# SOC_MIPI-CSI_I2C.net
KiCad netlist of a schematic drawn in Altium Designer
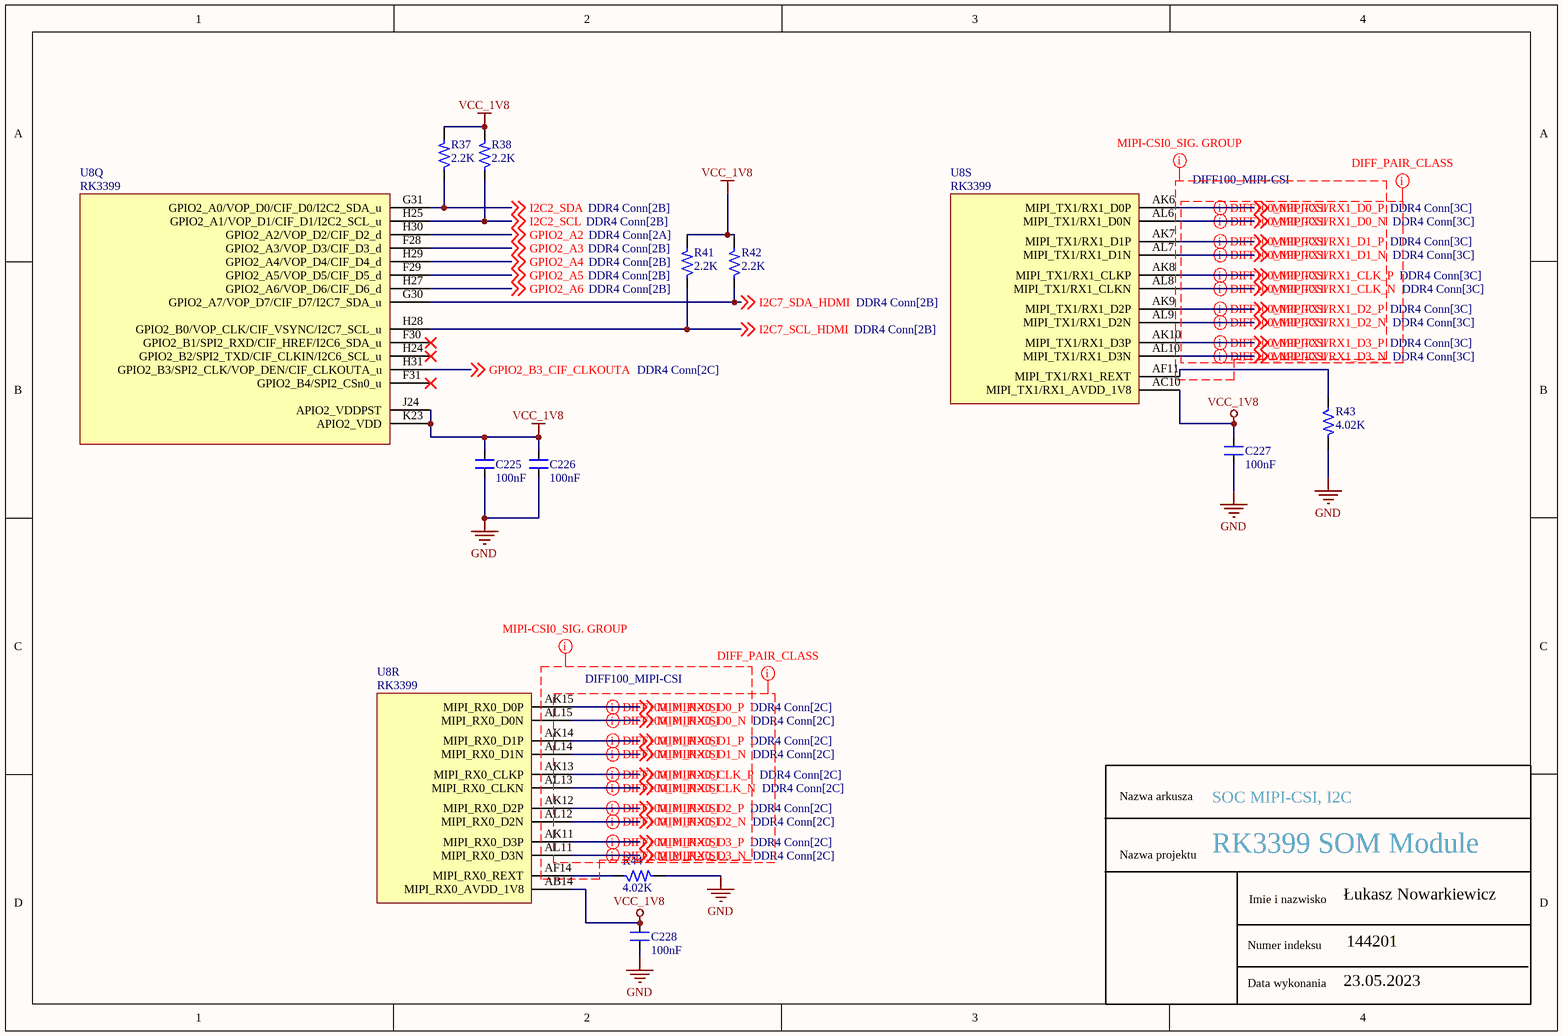
[diagram p0: SOC MIPI-CSI, I2C.SchDoc]

(export (version "E")
  (design (tool "Eeschema 10.0.6"))
  (components
    (comp (ref "C225")
      (value "100nF")
      (footprint "CAP_0201")
      (description "0.1µF ±10% 25V Ceramic Capacitor X5R 0201 (0603 Metric)")
      (fields
        (field (name "MANUFACTURER") "TDK Corporation")
        (field (name "MANUFACTURER PART NUMBER") "C0603X5R1E104K030BB")
      )
      (libsource (lib "RK3399 _Module_Intlib") (part "CAP_100nF-25V-10%-0201"))
    )
    (comp (ref "C226")
      (value "100nF")
      (footprint "CAP_0201")
      (description "0.1µF ±10% 25V Ceramic Capacitor X5R 0201 (0603 Metric)")
      (fields
        (field (name "MANUFACTURER") "TDK Corporation")
        (field (name "MANUFACTURER PART NUMBER") "C0603X5R1E104K030BB")
      )
      (libsource (lib "RK3399 _Module_Intlib") (part "CAP_100nF-25V-10%-0201"))
    )
    (comp (ref "C227")
      (value "100nF")
      (footprint "CAP_0201")
      (description "0.1µF ±10% 25V Ceramic Capacitor X5R 0201 (0603 Metric)")
      (fields
        (field (name "MANUFACTURER") "TDK Corporation")
        (field (name "MANUFACTURER PART NUMBER") "C0603X5R1E104K030BB")
      )
      (libsource (lib "RK3399 _Module_Intlib") (part "CAP_100nF-25V-10%-0201"))
    )
    (comp (ref "C228")
      (value "100nF")
      (footprint "CAP_0201")
      (description "0.1µF ±10% 25V Ceramic Capacitor X5R 0201 (0603 Metric)")
      (fields
        (field (name "MANUFACTURER") "TDK Corporation")
        (field (name "MANUFACTURER PART NUMBER") "C0603X5R1E104K030BB")
      )
      (libsource (lib "RK3399 _Module_Intlib") (part "CAP_100nF-25V-10%-0201"))
    )
    (comp (ref "R37")
      (value "2.2K")
      (footprint "RES_0201")
      (description "2.2 kOhms ±1% 0.05W, 1/20W Chip Resistor 0201 (0603 Metric) Thick Film")
      (fields
        (field (name "MANUFACTURER") "Stackpole Electronics Inc")
        (field (name "MANUFACTURER PART NUMBER") "RMCF0201FT2K20")
      )
      (libsource (lib "RK3399 _Module_Intlib") (part "RES_2.2K-0.05W-1%-0201"))
    )
    (comp (ref "R38")
      (value "2.2K")
      (footprint "RES_0201")
      (description "2.2 kOhms ±1% 0.05W, 1/20W Chip Resistor 0201 (0603 Metric) Thick Film")
      (fields
        (field (name "MANUFACTURER") "Stackpole Electronics Inc")
        (field (name "MANUFACTURER PART NUMBER") "RMCF0201FT2K20")
      )
      (libsource (lib "RK3399 _Module_Intlib") (part "RES_2.2K-0.05W-1%-0201"))
    )
    (comp (ref "R41")
      (value "2.2K")
      (footprint "RES_0201")
      (description "2.2 kOhms ±1% 0.05W, 1/20W Chip Resistor 0201 (0603 Metric) Thick Film")
      (fields
        (field (name "MANUFACTURER") "Stackpole Electronics Inc")
        (field (name "MANUFACTURER PART NUMBER") "RMCF0201FT2K20")
      )
      (libsource (lib "RK3399 _Module_Intlib") (part "RES_2.2K-0.05W-1%-0201"))
    )
    (comp (ref "R42")
      (value "2.2K")
      (footprint "RES_0201")
      (description "2.2 kOhms ±1% 0.05W, 1/20W Chip Resistor 0201 (0603 Metric) Thick Film")
      (fields
        (field (name "MANUFACTURER") "Stackpole Electronics Inc")
        (field (name "MANUFACTURER PART NUMBER") "RMCF0201FT2K20")
      )
      (libsource (lib "RK3399 _Module_Intlib") (part "RES_2.2K-0.05W-1%-0201"))
    )
    (comp (ref "R43")
      (value "4.02K")
      (footprint "RES_0201")
      (description "4.02 kOhms ±1% 0.05W, 1/20W Chip Resistor 0201 (0603 Metric) Thick Film")
      (fields
        (field (name "MANUFACTURER") "Yageo")
        (field (name "MANUFACTURER PART NUMBER") "RC0201FR-074K02L")
      )
      (libsource (lib "RK3399 _Module_Intlib") (part "RES_4.02K-0.05W-1%-0201"))
    )
    (comp (ref "R44")
      (value "4.02K")
      (footprint "RES_0201")
      (description "4.02 kOhms ±1% 0.05W, 1/20W Chip Resistor 0201 (0603 Metric) Thick Film")
      (fields
        (field (name "MANUFACTURER") "Yageo")
        (field (name "MANUFACTURER PART NUMBER") "RC0201FR-074K02L")
      )
      (libsource (lib "RK3399 _Module_Intlib") (part "RES_4.02K-0.05W-1%-0201"))
    )
    (comp (ref "U8")
      (value "RK3399")
      (footprint "FBGA828_23_826X826")
      (description "RK3399 is a low power, high performance processor for computing, personal mobile.")
      (fields (field (name "MANUFACTURER") "Rockchip"))
      (libsource (lib "EsteemPCB_SOM_Course_intlib") (part "IC_RK3399-FCBGA828"))
    )
  )
  (nets
    (net (code "1") (name "GND") (class "Default")
      (node (ref "C225") (pin "1") (pinfunction "1_1") (pintype "passive"))
      (node (ref "C226") (pin "1") (pinfunction "1_1") (pintype "passive"))
      (node (ref "C227") (pin "1") (pinfunction "1_1") (pintype "passive"))
      (node (ref "C228") (pin "1") (pinfunction "1_1") (pintype "passive"))
      (node (ref "R43") (pin "2") (pinfunction "2_2") (pintype "passive"))
      (node (ref "R44") (pin "2") (pinfunction "2_2") (pintype "passive"))
    )
    (net (code "2") (name "GPIO2_A2") (class "Default")
      (node (ref "U8") (pin "H30") (pinfunction "GPIO2_A2/VOP_D2/CIF_D2_d_H30") (pintype "passive"))
    )
    (net (code "3") (name "GPIO2_A3") (class "Default")
      (node (ref "U8") (pin "F28") (pinfunction "GPIO2_A3/VOP_D3/CIF_D3_d_F28") (pintype "passive"))
    )
    (net (code "4") (name "GPIO2_A4") (class "Default")
      (node (ref "U8") (pin "H29") (pinfunction "GPIO2_A4/VOP_D4/CIF_D4_d_H29") (pintype "passive"))
    )
    (net (code "5") (name "GPIO2_A5") (class "Default")
      (node (ref "U8") (pin "F29") (pinfunction "GPIO2_A5/VOP_D5/CIF_D5_d_F29") (pintype "passive"))
    )
    (net (code "6") (name "GPIO2_A6") (class "Default")
      (node (ref "U8") (pin "H27") (pinfunction "GPIO2_A6/VOP_D6/CIF_D6_d_H27") (pintype "passive"))
    )
    (net (code "7") (name "GPIO2_B3_CIF_CLKOUTA") (class "Default")
      (node (ref "U8") (pin "H31") (pinfunction "GPIO2_B3/SPI2_CLK/VOP_DEN/CIF_CLKOUTA_u_H31") (pintype "passive"))
    )
    (net (code "8") (name "I2C2_SCL") (class "Default")
      (node (ref "R38") (pin "1") (pinfunction "1_1") (pintype "passive"))
      (node (ref "U8") (pin "H25") (pinfunction "GPIO2_A1/VOP_D1/CIF_D1/I2C2_SCL_u_H25") (pintype "passive"))
    )
    (net (code "9") (name "I2C2_SDA") (class "Default")
      (node (ref "R37") (pin "1") (pinfunction "1_1") (pintype "passive"))
      (node (ref "U8") (pin "G31") (pinfunction "GPIO2_A0/VOP_D0/CIF_D0/I2C2_SDA_u_G31") (pintype "passive"))
    )
    (net (code "10") (name "I2C7_SCL_HDMI") (class "Default")
      (node (ref "R41") (pin "1") (pinfunction "1_1") (pintype "passive"))
      (node (ref "U8") (pin "H28") (pinfunction "GPIO2_B0/VOP_CLK/CIF_VSYNC/I2C7_SCL_u_H28") (pintype "passive"))
    )
    (net (code "11") (name "I2C7_SDA_HDMI") (class "Default")
      (node (ref "R42") (pin "1") (pinfunction "1_1") (pintype "passive"))
      (node (ref "U8") (pin "G30") (pinfunction "GPIO2_A7/VOP_D7/CIF_D7/I2C7_SDA_u_G30") (pintype "passive"))
    )
    (net (code "12") (name "MIPI_RX0_CLK_N") (class "Default")
      (node (ref "U8") (pin "AL13") (pinfunction "MIPI_RX0_CLKN_AL13") (pintype "passive"))
    )
    (net (code "13") (name "MIPI_RX0_CLK_P") (class "Default")
      (node (ref "U8") (pin "AK13") (pinfunction "MIPI_RX0_CLKP_AK13") (pintype "passive"))
    )
    (net (code "14") (name "MIPI_RX0_D0_N") (class "Default")
      (node (ref "U8") (pin "AL15") (pinfunction "MIPI_RX0_D0N_AL15") (pintype "passive"))
    )
    (net (code "15") (name "MIPI_RX0_D0_P") (class "Default")
      (node (ref "U8") (pin "AK15") (pinfunction "MIPI_RX0_D0P_AK15") (pintype "passive"))
    )
    (net (code "16") (name "MIPI_RX0_D1_N") (class "Default")
      (node (ref "U8") (pin "AL14") (pinfunction "MIPI_RX0_D1N_AL14") (pintype "passive"))
    )
    (net (code "17") (name "MIPI_RX0_D1_P") (class "Default")
      (node (ref "U8") (pin "AK14") (pinfunction "MIPI_RX0_D1P_AK14") (pintype "passive"))
    )
    (net (code "18") (name "MIPI_RX0_D2_N") (class "Default")
      (node (ref "U8") (pin "AL12") (pinfunction "MIPI_RX0_D2N_AL12") (pintype "passive"))
    )
    (net (code "19") (name "MIPI_RX0_D2_P") (class "Default")
      (node (ref "U8") (pin "AK12") (pinfunction "MIPI_RX0_D2P_AK12") (pintype "passive"))
    )
    (net (code "20") (name "MIPI_RX0_D3_N") (class "Default")
      (node (ref "U8") (pin "AL11") (pinfunction "MIPI_RX0_D3N_AL11") (pintype "passive"))
    )
    (net (code "21") (name "MIPI_RX0_D3_P") (class "Default")
      (node (ref "U8") (pin "AK11") (pinfunction "MIPI_RX0_D3P_AK11") (pintype "passive"))
    )
    (net (code "22") (name "MIPI_TX1{slash}RX1_CLK_N") (class "Default")
      (node (ref "U8") (pin "AL8") (pinfunction "MIPI_TX1/RX1_CLKN_AL8") (pintype "passive"))
    )
    (net (code "23") (name "MIPI_TX1{slash}RX1_CLK_P") (class "Default")
      (node (ref "U8") (pin "AK8") (pinfunction "MIPI_TX1/RX1_CLKP_AK8") (pintype "passive"))
    )
    (net (code "24") (name "MIPI_TX1{slash}RX1_D0_N") (class "Default")
      (node (ref "U8") (pin "AL6") (pinfunction "MIPI_TX1/RX1_D0N_AL6") (pintype "passive"))
    )
    (net (code "25") (name "MIPI_TX1{slash}RX1_D0_P") (class "Default")
      (node (ref "U8") (pin "AK6") (pinfunction "MIPI_TX1/RX1_D0P_AK6") (pintype "passive"))
    )
    (net (code "26") (name "MIPI_TX1{slash}RX1_D1_N") (class "Default")
      (node (ref "U8") (pin "AL7") (pinfunction "MIPI_TX1/RX1_D1N_AL7") (pintype "passive"))
    )
    (net (code "27") (name "MIPI_TX1{slash}RX1_D1_P") (class "Default")
      (node (ref "U8") (pin "AK7") (pinfunction "MIPI_TX1/RX1_D1P_AK7") (pintype "passive"))
    )
    (net (code "28") (name "MIPI_TX1{slash}RX1_D2_N") (class "Default")
      (node (ref "U8") (pin "AL9") (pinfunction "MIPI_TX1/RX1_D2N_AL9") (pintype "passive"))
    )
    (net (code "29") (name "MIPI_TX1{slash}RX1_D2_P") (class "Default")
      (node (ref "U8") (pin "AK9") (pinfunction "MIPI_TX1/RX1_D2P_AK9") (pintype "passive"))
    )
    (net (code "30") (name "MIPI_TX1{slash}RX1_D3_N") (class "Default")
      (node (ref "U8") (pin "AL10") (pinfunction "MIPI_TX1/RX1_D3N_AL10") (pintype "passive"))
    )
    (net (code "31") (name "MIPI_TX1{slash}RX1_D3_P") (class "Default")
      (node (ref "U8") (pin "AK10") (pinfunction "MIPI_TX1/RX1_D3P_AK10") (pintype "passive"))
    )
    (net (code "32") (name "Net-(U8R-MIPI_RX0_REXT)") (class "Default")
      (node (ref "R44") (pin "1") (pinfunction "1_1") (pintype "passive"))
      (node (ref "U8") (pin "AF14") (pinfunction "MIPI_RX0_REXT_AF14") (pintype "passive"))
    )
    (net (code "33") (name "Net-(U8S-MIPI_TX1{slash}RX1_REXT)") (class "Default")
      (node (ref "R43") (pin "1") (pinfunction "1_1") (pintype "passive"))
      (node (ref "U8") (pin "AF11") (pinfunction "MIPI_TX1/RX1_REXT_AF11") (pintype "passive"))
    )
    (net (code "34") (name "VCC_1V8") (class "Default")
      (node (ref "C225") (pin "2") (pinfunction "2_2") (pintype "passive"))
      (node (ref "C226") (pin "2") (pinfunction "2_2") (pintype "passive"))
      (node (ref "C227") (pin "2") (pinfunction "2_2") (pintype "passive"))
      (node (ref "C228") (pin "2") (pinfunction "2_2") (pintype "passive"))
      (node (ref "R37") (pin "2") (pinfunction "2_2") (pintype "passive"))
      (node (ref "R38") (pin "2") (pinfunction "2_2") (pintype "passive"))
      (node (ref "R41") (pin "2") (pinfunction "2_2") (pintype "passive"))
      (node (ref "R42") (pin "2") (pinfunction "2_2") (pintype "passive"))
      (node (ref "U8") (pin "AB14") (pinfunction "MIPI_RX0_AVDD_1V8_AB14") (pintype "passive"))
      (node (ref "U8") (pin "AC10") (pinfunction "MIPI_TX1/RX1_AVDD_1V8_AC10") (pintype "passive"))
      (node (ref "U8") (pin "J24") (pinfunction "APIO2_VDDPST_J24") (pintype "passive"))
      (node (ref "U8") (pin "K23") (pinfunction "APIO2_VDD_K23") (pintype "passive"))
    )
    (net (code "35") (name "unconnected-(U8Q-GPIO2_B1{slash}SPI2_RXD{slash}CIF_HREF{slash}I2C6_SDA_u-PadF30)") (class "Default")
      (node (ref "U8") (pin "F30") (pinfunction "GPIO2_B1/SPI2_RXD/CIF_HREF/I2C6_SDA_u_F30") (pintype "passive+no_connect"))
    )
    (net (code "36") (name "unconnected-(U8Q-GPIO2_B2{slash}SPI2_TXD{slash}CIF_CLKIN{slash}I2C6_SCL_u-PadH24)") (class "Default")
      (node (ref "U8") (pin "H24") (pinfunction "GPIO2_B2/SPI2_TXD/CIF_CLKIN/I2C6_SCL_u_H24") (pintype "passive+no_connect"))
    )
    (net (code "37") (name "unconnected-(U8Q-GPIO2_B4{slash}SPI2_CSn0_u-PadF31)") (class "Default")
      (node (ref "U8") (pin "F31") (pinfunction "GPIO2_B4/SPI2_CSn0_u_F31") (pintype "passive+no_connect"))
    )
  )
)
